# TinyHusk.net
KiCad netlist of a schematic drawn in EAGLE
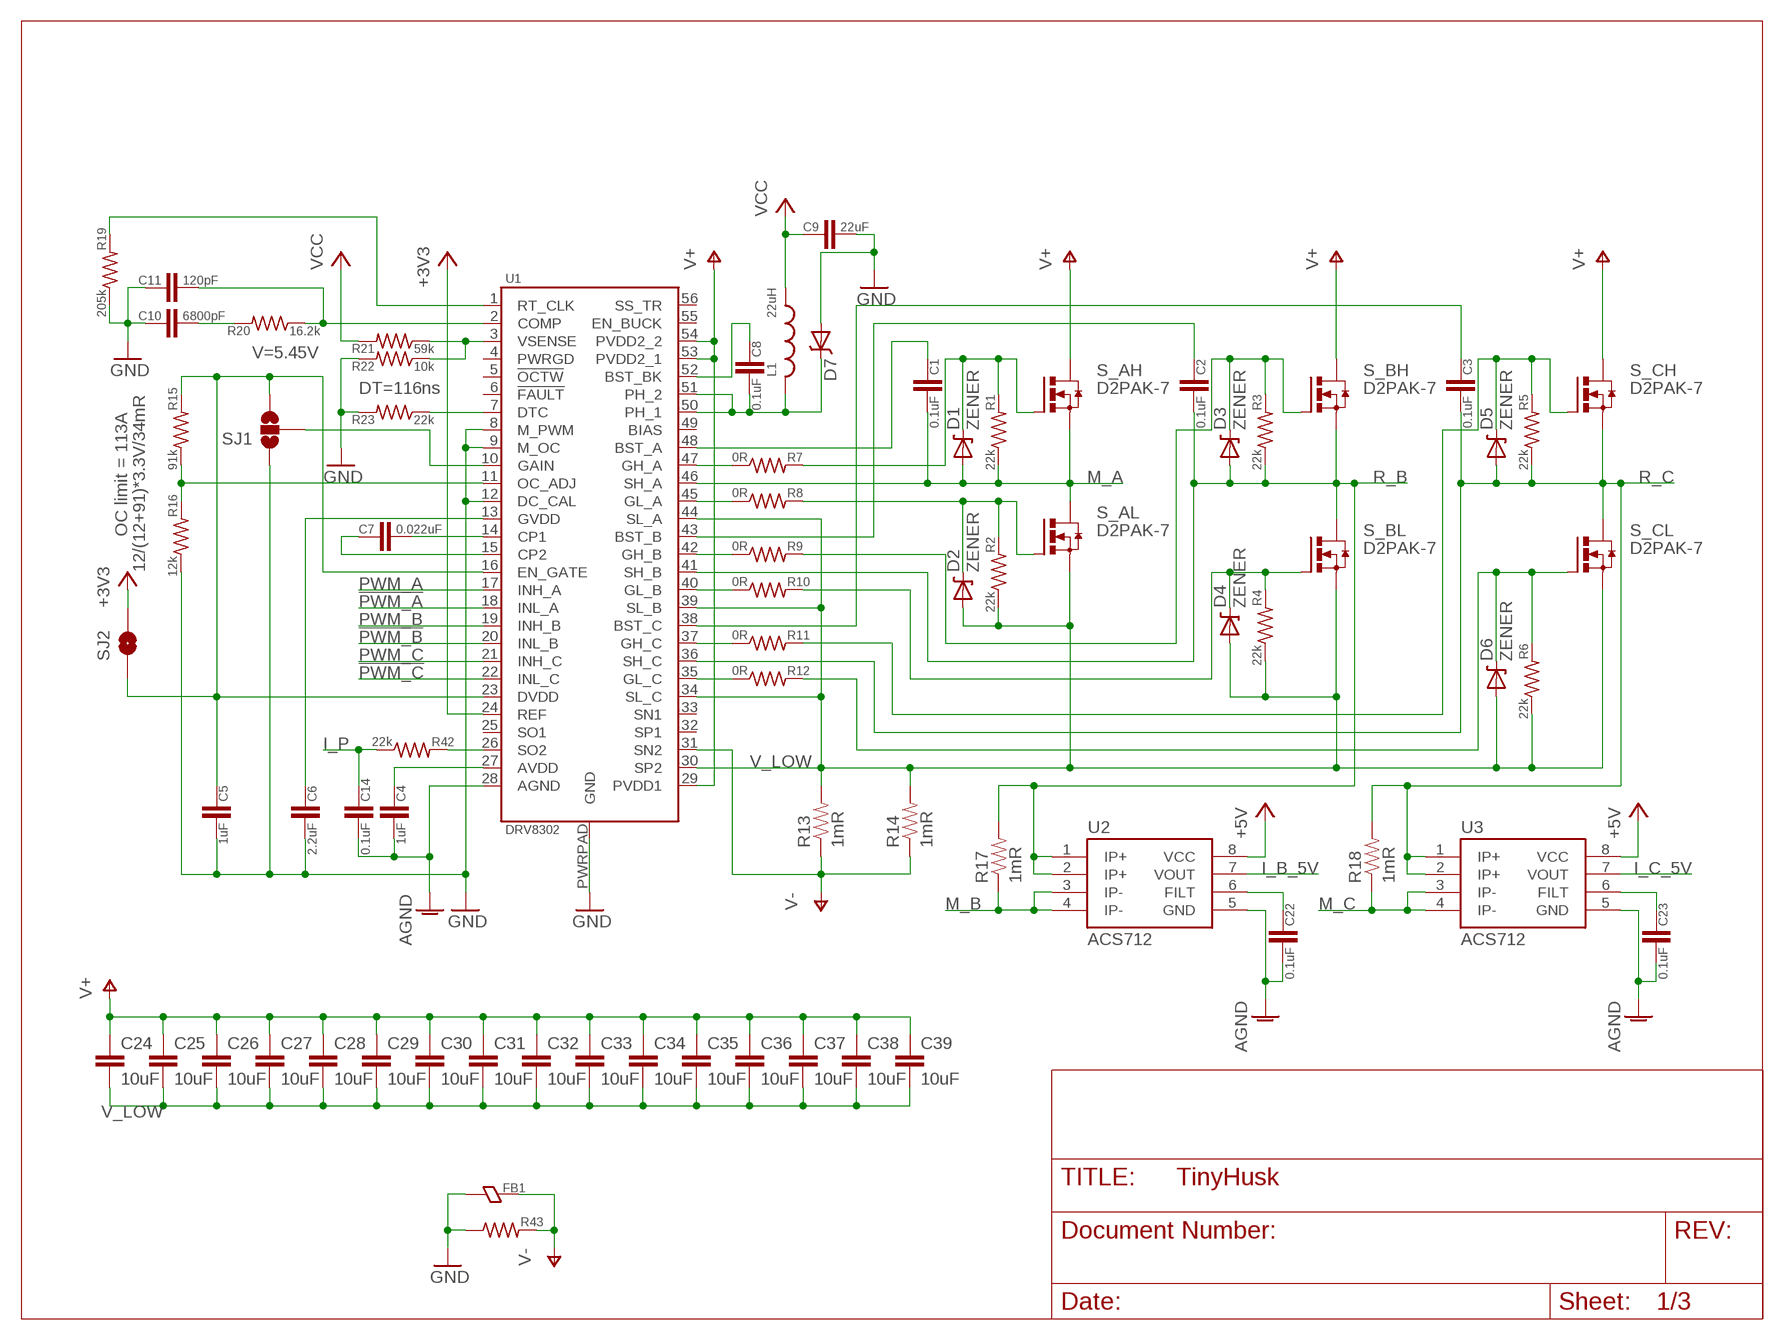
[diagram p0: schematic, sheet 1]
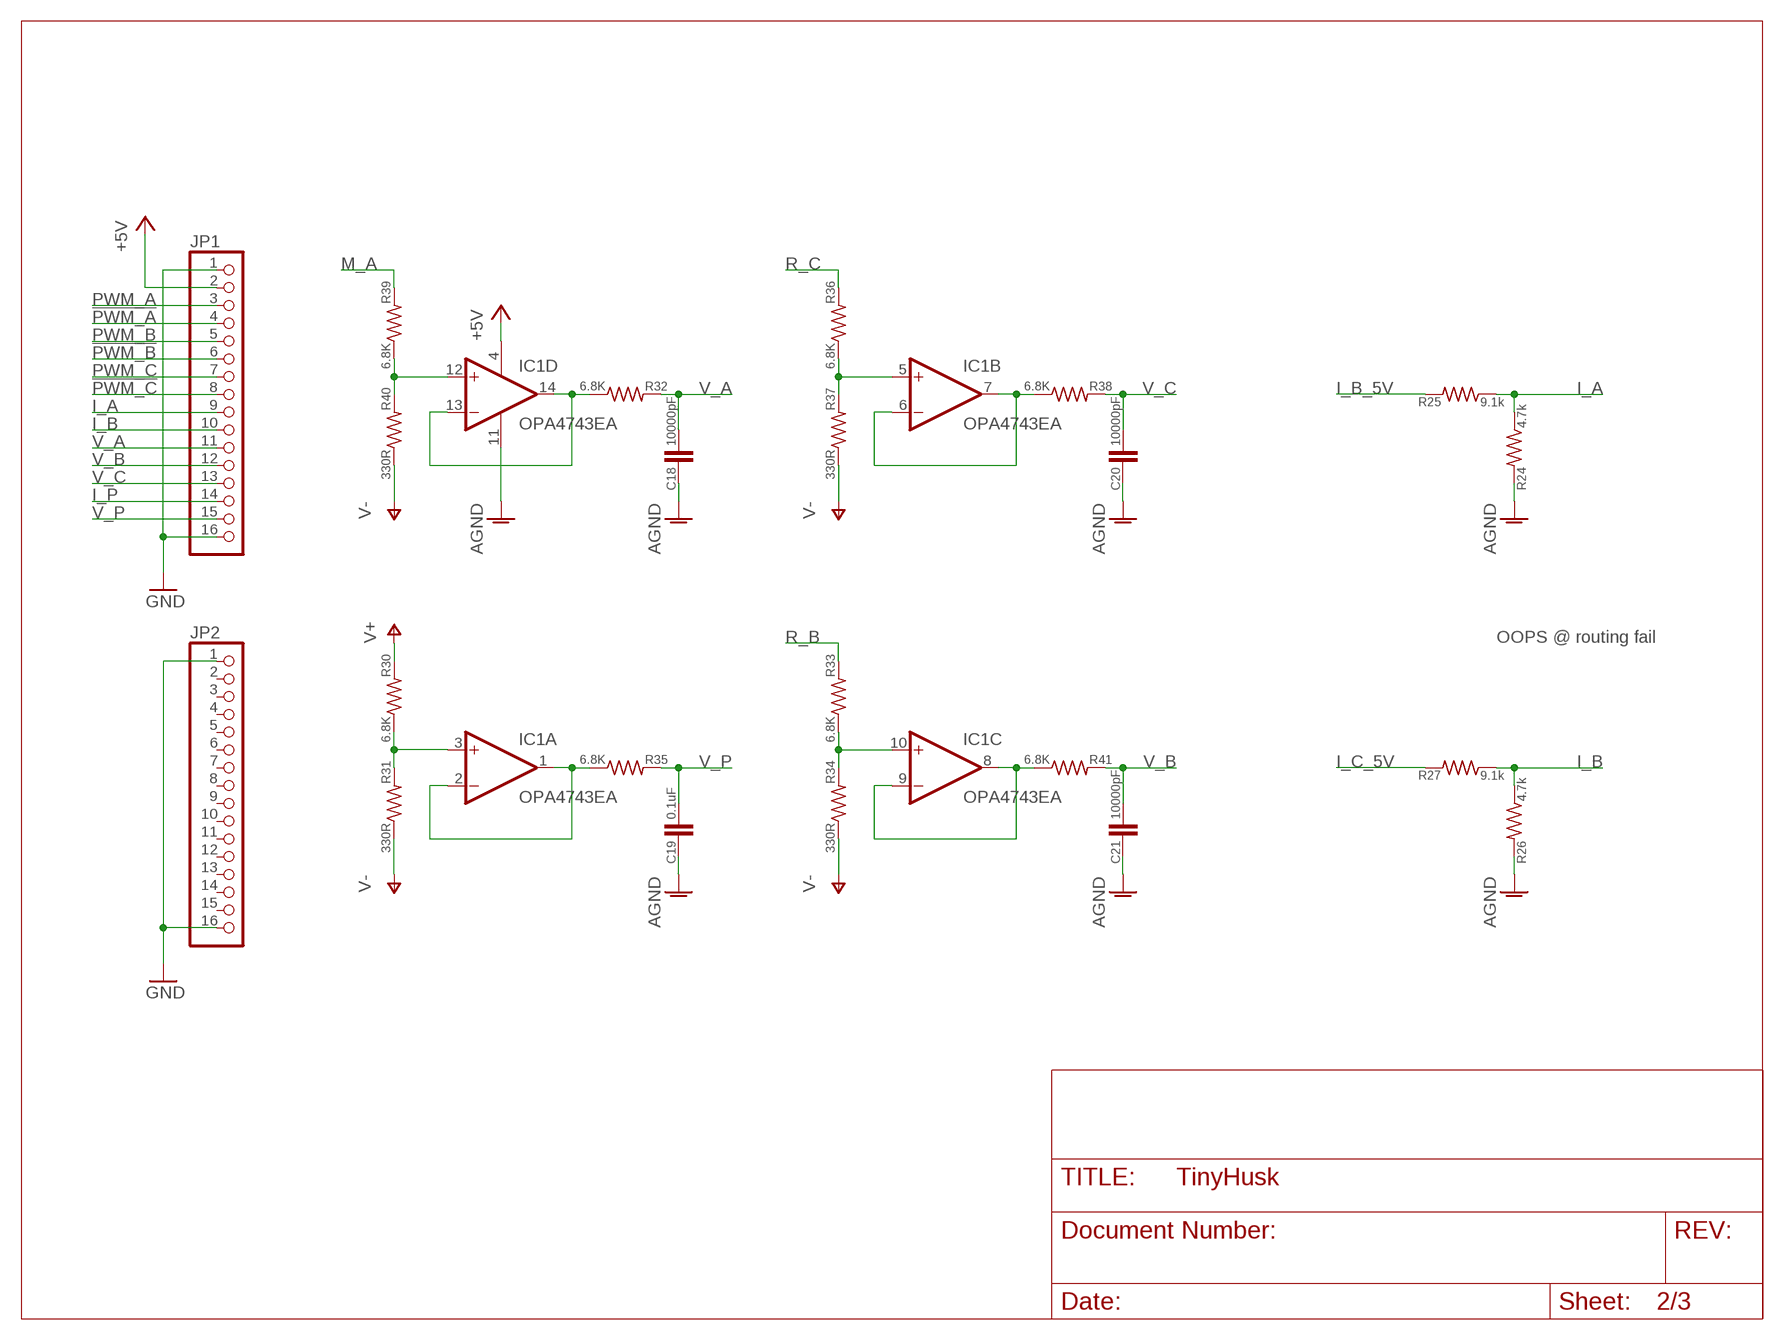
[diagram p1: schematic, sheet 2]
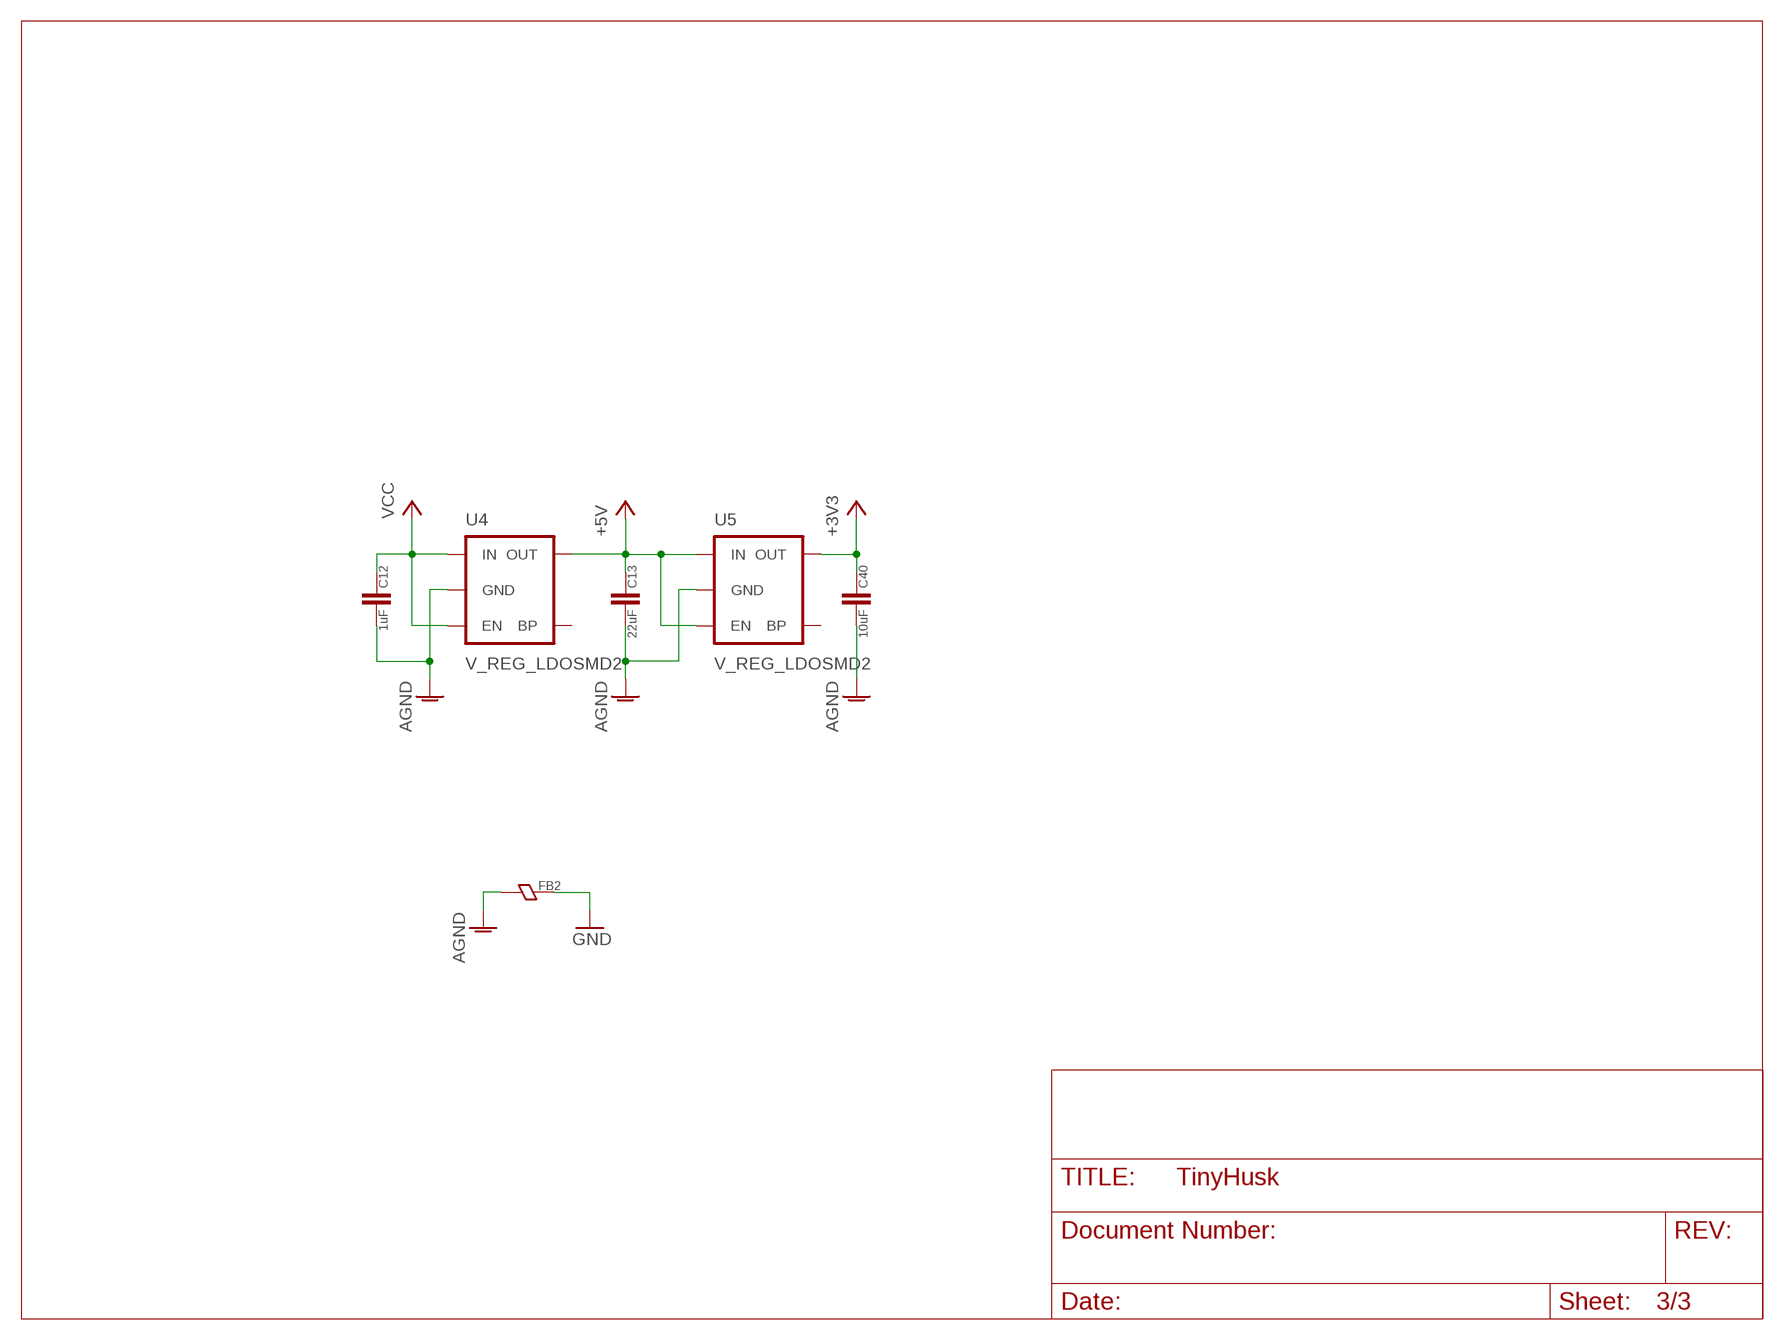
[diagram p2: schematic, sheet 3]

(export (version "E")
  (design (tool "Eeschema 10.0.6"))
  (components
    (comp (ref "C1")
      (value "0.1uF")
      (footprint "eagle-import:0603")
      (libsource (lib "eagle-import") (part "C0603"))
    )
    (comp (ref "C2")
      (value "0.1uF")
      (footprint "eagle-import:0603")
      (libsource (lib "eagle-import") (part "C0603"))
    )
    (comp (ref "C3")
      (value "0.1uF")
      (footprint "eagle-import:0603")
      (libsource (lib "eagle-import") (part "C0603"))
    )
    (comp (ref "C4")
      (value "1uF")
      (footprint "eagle-import:0603")
      (libsource (lib "eagle-import") (part "C0603"))
    )
    (comp (ref "C5")
      (value "1uF")
      (footprint "eagle-import:0603")
      (libsource (lib "eagle-import") (part "C0603"))
    )
    (comp (ref "C6")
      (value "2.2uF")
      (footprint "eagle-import:0603")
      (libsource (lib "eagle-import") (part "C0603"))
    )
    (comp (ref "C7")
      (value "0.022uF")
      (footprint "eagle-import:0603")
      (libsource (lib "eagle-import") (part "C0603"))
    )
    (comp (ref "C8")
      (value "0.1uF")
      (footprint "eagle-import:0603")
      (libsource (lib "eagle-import") (part "C0603"))
    )
    (comp (ref "C9")
      (value "22uF")
      (footprint "eagle-import:0805")
      (libsource (lib "eagle-import") (part "C0805"))
    )
    (comp (ref "C10")
      (value "6800pF")
      (footprint "eagle-import:0603")
      (libsource (lib "eagle-import") (part "C0603"))
    )
    (comp (ref "C11")
      (value "120pF")
      (footprint "eagle-import:0603")
      (libsource (lib "eagle-import") (part "C0603"))
    )
    (comp (ref "C14")
      (value "0.1uF")
      (footprint "eagle-import:0603")
      (libsource (lib "eagle-import") (part "C0603"))
    )
    (comp (ref "C22")
      (value "0.1uF")
      (footprint "eagle-import:0603")
      (libsource (lib "eagle-import") (part "C0603"))
    )
    (comp (ref "C23")
      (value "0.1uF")
      (footprint "eagle-import:0603")
      (libsource (lib "eagle-import") (part "C0603"))
    )
    (comp (ref "C24")
      (value "10uF")
      (footprint "eagle-import:1210")
      (libsource (lib "eagle-import") (part "CAP1210"))
    )
    (comp (ref "C25")
      (value "10uF")
      (footprint "eagle-import:1210")
      (libsource (lib "eagle-import") (part "CAP1210"))
    )
    (comp (ref "C26")
      (value "10uF")
      (footprint "eagle-import:1210")
      (libsource (lib "eagle-import") (part "CAP1210"))
    )
    (comp (ref "C27")
      (value "10uF")
      (footprint "eagle-import:1210")
      (libsource (lib "eagle-import") (part "CAP1210"))
    )
    (comp (ref "C28")
      (value "10uF")
      (footprint "eagle-import:1210")
      (libsource (lib "eagle-import") (part "CAP1210"))
    )
    (comp (ref "C29")
      (value "10uF")
      (footprint "eagle-import:1210")
      (libsource (lib "eagle-import") (part "CAP1210"))
    )
    (comp (ref "C30")
      (value "10uF")
      (footprint "eagle-import:1210")
      (libsource (lib "eagle-import") (part "CAP1210"))
    )
    (comp (ref "C31")
      (value "10uF")
      (footprint "eagle-import:1210")
      (libsource (lib "eagle-import") (part "CAP1210"))
    )
    (comp (ref "C32")
      (value "10uF")
      (footprint "eagle-import:1210")
      (libsource (lib "eagle-import") (part "CAP1210"))
    )
    (comp (ref "C33")
      (value "10uF")
      (footprint "eagle-import:1210")
      (libsource (lib "eagle-import") (part "CAP1210"))
    )
    (comp (ref "C34")
      (value "10uF")
      (footprint "eagle-import:1210")
      (libsource (lib "eagle-import") (part "CAP1210"))
    )
    (comp (ref "C35")
      (value "10uF")
      (footprint "eagle-import:1210")
      (libsource (lib "eagle-import") (part "CAP1210"))
    )
    (comp (ref "C36")
      (value "10uF")
      (footprint "eagle-import:1210")
      (libsource (lib "eagle-import") (part "CAP1210"))
    )
    (comp (ref "C37")
      (value "10uF")
      (footprint "eagle-import:1210")
      (libsource (lib "eagle-import") (part "CAP1210"))
    )
    (comp (ref "C38")
      (value "10uF")
      (footprint "eagle-import:1210")
      (libsource (lib "eagle-import") (part "CAP1210"))
    )
    (comp (ref "C39")
      (value "10uF")
      (footprint "eagle-import:1210")
      (libsource (lib "eagle-import") (part "CAP1210"))
    )
    (comp (ref "D1")
      (value "ZENER")
      (footprint "eagle-import:SOD-323")
      (libsource (lib "eagle-import") (part "DIODE-ZENER-BZT52"))
    )
    (comp (ref "D2")
      (value "ZENER")
      (footprint "eagle-import:SOD-323")
      (libsource (lib "eagle-import") (part "DIODE-ZENER-BZT52"))
    )
    (comp (ref "D3")
      (value "ZENER")
      (footprint "eagle-import:SOD-323")
      (libsource (lib "eagle-import") (part "DIODE-ZENER-BZT52"))
    )
    (comp (ref "D4")
      (value "ZENER")
      (footprint "eagle-import:SOD-323")
      (libsource (lib "eagle-import") (part "DIODE-ZENER-BZT52"))
    )
    (comp (ref "D5")
      (value "ZENER")
      (footprint "eagle-import:SOD-323")
      (libsource (lib "eagle-import") (part "DIODE-ZENER-BZT52"))
    )
    (comp (ref "D6")
      (value "ZENER")
      (footprint "eagle-import:SOD-323")
      (libsource (lib "eagle-import") (part "DIODE-ZENER-BZT52"))
    )
    (comp (ref "D7")
      (value "DIODE-SCHOTTKY_")
      (footprint "eagle-import:SMA-DIODE")
      (libsource (lib "eagle-import") (part "DIODE-SCHOTTKY_"))
    )
    (comp (ref "FB1")
      (value "FERRITE0603")
      (footprint "eagle-import:0603")
      (libsource (lib "eagle-import") (part "FERRITE0603"))
    )
    (comp (ref "L1")
      (value "22uH")
      (footprint "eagle-import:TAIYO-YUDEN_NR50")
      (libsource (lib "eagle-import") (part "L-US_TAIYO-YUDEN_NR50"))
    )
    (comp (ref "R1")
      (value "22k")
      (footprint "eagle-import:0603")
      (libsource (lib "eagle-import") (part "R0603"))
    )
    (comp (ref "R2")
      (value "22k")
      (footprint "eagle-import:0603")
      (libsource (lib "eagle-import") (part "R0603"))
    )
    (comp (ref "R3")
      (value "22k")
      (footprint "eagle-import:0603")
      (libsource (lib "eagle-import") (part "R0603"))
    )
    (comp (ref "R4")
      (value "22k")
      (footprint "eagle-import:0603")
      (libsource (lib "eagle-import") (part "R0603"))
    )
    (comp (ref "R5")
      (value "22k")
      (footprint "eagle-import:0603")
      (libsource (lib "eagle-import") (part "R0603"))
    )
    (comp (ref "R6")
      (value "22k")
      (footprint "eagle-import:0603")
      (libsource (lib "eagle-import") (part "R0603"))
    )
    (comp (ref "R7")
      (value "0R")
      (footprint "eagle-import:0603")
      (libsource (lib "eagle-import") (part "R0603"))
    )
    (comp (ref "R8")
      (value "0R")
      (footprint "eagle-import:0603")
      (libsource (lib "eagle-import") (part "R0603"))
    )
    (comp (ref "R9")
      (value "0R")
      (footprint "eagle-import:0603")
      (libsource (lib "eagle-import") (part "R0603"))
    )
    (comp (ref "R10")
      (value "0R")
      (footprint "eagle-import:0603")
      (libsource (lib "eagle-import") (part "R0603"))
    )
    (comp (ref "R11")
      (value "0R")
      (footprint "eagle-import:0603")
      (libsource (lib "eagle-import") (part "R0603"))
    )
    (comp (ref "R12")
      (value "0R")
      (footprint "eagle-import:0603")
      (libsource (lib "eagle-import") (part "R0603"))
    )
    (comp (ref "R13")
      (value "1mR")
      (footprint "eagle-import:R2512")
      (libsource (lib "eagle-import") (part "RESISTOR2512"))
    )
    (comp (ref "R14")
      (value "1mR")
      (footprint "eagle-import:R2512")
      (libsource (lib "eagle-import") (part "RESISTOR2512"))
    )
    (comp (ref "R15")
      (value "91k")
      (footprint "eagle-import:0603")
      (libsource (lib "eagle-import") (part "R0603"))
    )
    (comp (ref "R16")
      (value "12k")
      (footprint "eagle-import:0603")
      (libsource (lib "eagle-import") (part "R0603"))
    )
    (comp (ref "R17")
      (value "1mR")
      (footprint "eagle-import:R2512")
      (libsource (lib "eagle-import") (part "RESISTOR2512"))
    )
    (comp (ref "R18")
      (value "1mR")
      (footprint "eagle-import:R2512")
      (libsource (lib "eagle-import") (part "RESISTOR2512"))
    )
    (comp (ref "R19")
      (value "205k")
      (footprint "eagle-import:0603")
      (libsource (lib "eagle-import") (part "R0603"))
    )
    (comp (ref "R20")
      (value "16.2k")
      (footprint "eagle-import:0603")
      (libsource (lib "eagle-import") (part "R0603"))
    )
    (comp (ref "R21")
      (value "59k")
      (footprint "eagle-import:0603")
      (libsource (lib "eagle-import") (part "R0603"))
    )
    (comp (ref "R22")
      (value "10k")
      (footprint "eagle-import:0603")
      (libsource (lib "eagle-import") (part "R0603"))
    )
    (comp (ref "R23")
      (value "22k")
      (footprint "eagle-import:0603")
      (libsource (lib "eagle-import") (part "R0603"))
    )
    (comp (ref "R42")
      (value "22k")
      (footprint "eagle-import:0603")
      (libsource (lib "eagle-import") (part "R0603"))
    )
    (comp (ref "R43")
      (value "R0603")
      (footprint "eagle-import:0603")
      (libsource (lib "eagle-import") (part "R0603"))
    )
    (comp (ref "SJ1")
      (value "SOLDERJUMPER_2WAYS")
      (footprint "eagle-import:SJ_X")
      (libsource (lib "eagle-import") (part "SOLDERJUMPER_2WAYS"))
    )
    (comp (ref "SJ2")
      (value "SOLDERJUMPERTRACE")
      (footprint "eagle-import:SJ_2S-TRACE")
      (libsource (lib "eagle-import") (part "SOLDERJUMPERTRACE"))
    )
    (comp (ref "S_AH")
      (value "D2PAK-7")
      (footprint "eagle-import:D2PAK-7")
      (libsource (lib "eagle-import") (part "MOSFET-ND2PAK7"))
    )
    (comp (ref "S_AL")
      (value "D2PAK-7")
      (footprint "eagle-import:D2PAK-7")
      (libsource (lib "eagle-import") (part "MOSFET-ND2PAK7"))
    )
    (comp (ref "S_BH")
      (value "D2PAK-7")
      (footprint "eagle-import:D2PAK-7")
      (libsource (lib "eagle-import") (part "MOSFET-ND2PAK7"))
    )
    (comp (ref "S_BL")
      (value "D2PAK-7")
      (footprint "eagle-import:D2PAK-7")
      (libsource (lib "eagle-import") (part "MOSFET-ND2PAK7"))
    )
    (comp (ref "S_CH")
      (value "D2PAK-7")
      (footprint "eagle-import:D2PAK-7")
      (libsource (lib "eagle-import") (part "MOSFET-ND2PAK7"))
    )
    (comp (ref "S_CL")
      (value "D2PAK-7")
      (footprint "eagle-import:D2PAK-7")
      (libsource (lib "eagle-import") (part "MOSFET-ND2PAK7"))
    )
    (comp (ref "U1")
      (value "DRV8302")
      (footprint "eagle-import:HTSSOP-56")
      (libsource (lib "eagle-import") (part "DRV8302"))
    )
    (comp (ref "U2")
      (value "ACS712")
      (footprint "eagle-import:SO08")
      (libsource (lib "eagle-import") (part "ACS712"))
    )
    (comp (ref "U3")
      (value "ACS712")
      (footprint "eagle-import:SO08")
      (libsource (lib "eagle-import") (part "ACS712"))
    )
    (comp (ref "C12")
      (value "1uF")
      (footprint "eagle-import:0603")
      (libsource (lib "eagle-import") (part "C0603"))
    )
    (comp (ref "C13")
      (value "22uF")
      (footprint "eagle-import:0805")
      (libsource (lib "eagle-import") (part "C0805"))
    )
    (comp (ref "C40")
      (value "10uF")
      (footprint "eagle-import:0603")
      (libsource (lib "eagle-import") (part "C0603"))
    )
    (comp (ref "FB2")
      (value "FERRITE0603")
      (footprint "eagle-import:0603")
      (libsource (lib "eagle-import") (part "FERRITE0603"))
    )
    (comp (ref "U4")
      (value "V_REG_LDOSMD2")
      (footprint "eagle-import:SC70")
      (libsource (lib "eagle-import") (part "V_REG_LDOSMD2"))
    )
    (comp (ref "U5")
      (value "V_REG_LDOSMD2")
      (footprint "eagle-import:SC70")
      (libsource (lib "eagle-import") (part "V_REG_LDOSMD2"))
    )
    (comp (ref "C18")
      (value "10000pF")
      (footprint "eagle-import:0603")
      (libsource (lib "eagle-import") (part "C0603"))
    )
    (comp (ref "C19")
      (value "0.1uF")
      (footprint "eagle-import:0603")
      (libsource (lib "eagle-import") (part "C0603"))
    )
    (comp (ref "C20")
      (value "10000pF")
      (footprint "eagle-import:0603")
      (libsource (lib "eagle-import") (part "C0603"))
    )
    (comp (ref "C21")
      (value "10000pF")
      (footprint "eagle-import:0603")
      (libsource (lib "eagle-import") (part "C0603"))
    )
    (comp (ref "IC1")
      (value "OPA4743EA")
      (footprint "eagle-import:TSSOP14")
      (libsource (lib "eagle-import") (part "OPA4743EA"))
    )
    (comp (ref "JP1")
      (value "PINHD-1X16_2.54-S")
      (footprint "eagle-import:1X16-S")
      (libsource (lib "eagle-import") (part "PINHD-1X16_2.54-S"))
    )
    (comp (ref "JP2")
      (value "PINHD-1X16_2.54-S")
      (footprint "eagle-import:1X16-S")
      (libsource (lib "eagle-import") (part "PINHD-1X16_2.54-S"))
    )
    (comp (ref "R24")
      (value "4.7k")
      (footprint "eagle-import:0603")
      (libsource (lib "eagle-import") (part "R0603"))
    )
    (comp (ref "R25")
      (value "9.1k")
      (footprint "eagle-import:0603")
      (libsource (lib "eagle-import") (part "R0603"))
    )
    (comp (ref "R26")
      (value "4.7k")
      (footprint "eagle-import:0603")
      (libsource (lib "eagle-import") (part "R0603"))
    )
    (comp (ref "R27")
      (value "9.1k")
      (footprint "eagle-import:0603")
      (libsource (lib "eagle-import") (part "R0603"))
    )
    (comp (ref "R30")
      (value "6.8K")
      (footprint "eagle-import:0603")
      (libsource (lib "eagle-import") (part "R0603"))
    )
    (comp (ref "R31")
      (value "330R")
      (footprint "eagle-import:0603")
      (libsource (lib "eagle-import") (part "R0603"))
    )
    (comp (ref "R32")
      (value "6.8K")
      (footprint "eagle-import:0603")
      (libsource (lib "eagle-import") (part "R0603"))
    )
    (comp (ref "R33")
      (value "6.8K")
      (footprint "eagle-import:0603")
      (libsource (lib "eagle-import") (part "R0603"))
    )
    (comp (ref "R34")
      (value "330R")
      (footprint "eagle-import:0603")
      (libsource (lib "eagle-import") (part "R0603"))
    )
    (comp (ref "R35")
      (value "6.8K")
      (footprint "eagle-import:0603")
      (libsource (lib "eagle-import") (part "R0603"))
    )
    (comp (ref "R36")
      (value "6.8K")
      (footprint "eagle-import:0603")
      (libsource (lib "eagle-import") (part "R0603"))
    )
    (comp (ref "R37")
      (value "330R")
      (footprint "eagle-import:0603")
      (libsource (lib "eagle-import") (part "R0603"))
    )
    (comp (ref "R38")
      (value "6.8K")
      (footprint "eagle-import:0603")
      (libsource (lib "eagle-import") (part "R0603"))
    )
    (comp (ref "R39")
      (value "6.8K")
      (footprint "eagle-import:0603")
      (libsource (lib "eagle-import") (part "R0603"))
    )
    (comp (ref "R40")
      (value "330R")
      (footprint "eagle-import:0603")
      (libsource (lib "eagle-import") (part "R0603"))
    )
    (comp (ref "R41")
      (value "6.8K")
      (footprint "eagle-import:0603")
      (libsource (lib "eagle-import") (part "R0603"))
    )
  )
  (nets
    (net (code "1") (name "+3V3") (class "Default")
      (node (ref "C40") (pin "1") (pinfunction "1_1") (pintype "passive"))
      (node (ref "SJ2") (pin "2") (pinfunction "2_2") (pintype "passive"))
      (node (ref "U1") (pin "24") (pinfunction "REF_24") (pintype "input"))
      (node (ref "U5") (pin "5") (pinfunction "OUT_5") (pintype "passive"))
    )
    (net (code "2") (name "+5V") (class "Default")
      (node (ref "C13") (pin "1") (pinfunction "1_1") (pintype "passive"))
      (node (ref "IC1") (pin "4") (pinfunction "V+_4") (pintype "power_in"))
      (node (ref "JP1") (pin "2") (pinfunction "2_2") (pintype "passive"))
      (node (ref "U2") (pin "8") (pinfunction "VCC_8") (pintype "bidirectional"))
      (node (ref "U3") (pin "8") (pinfunction "VCC_8") (pintype "bidirectional"))
      (node (ref "U4") (pin "5") (pinfunction "OUT_5") (pintype "passive"))
      (node (ref "U5") (pin "1") (pinfunction "IN_1") (pintype "input"))
      (node (ref "U5") (pin "3") (pinfunction "EN_3") (pintype "input"))
    )
    (net (code "3") (name "AGND") (class "Default")
      (node (ref "C12") (pin "2") (pinfunction "2_2") (pintype "passive"))
      (node (ref "C13") (pin "2") (pinfunction "2_2") (pintype "passive"))
      (node (ref "C14") (pin "2") (pinfunction "2_2") (pintype "passive"))
      (node (ref "C18") (pin "1") (pinfunction "1_1") (pintype "passive"))
      (node (ref "C19") (pin "1") (pinfunction "1_1") (pintype "passive"))
      (node (ref "C20") (pin "1") (pinfunction "1_1") (pintype "passive"))
      (node (ref "C21") (pin "1") (pinfunction "1_1") (pintype "passive"))
      (node (ref "C22") (pin "2") (pinfunction "2_2") (pintype "passive"))
      (node (ref "C23") (pin "2") (pinfunction "2_2") (pintype "passive"))
      (node (ref "C4") (pin "2") (pinfunction "2_2") (pintype "passive"))
      (node (ref "C40") (pin "2") (pinfunction "2_2") (pintype "passive"))
      (node (ref "FB2") (pin "1") (pinfunction "1_1") (pintype "passive"))
      (node (ref "IC1") (pin "11") (pinfunction "V-_11") (pintype "power_in"))
      (node (ref "R24") (pin "2") (pinfunction "2_2") (pintype "passive"))
      (node (ref "R26") (pin "2") (pinfunction "2_2") (pintype "passive"))
      (node (ref "U1") (pin "28") (pinfunction "AGND_28") (pintype "power_in"))
      (node (ref "U2") (pin "5") (pinfunction "GND_5") (pintype "bidirectional"))
      (node (ref "U3") (pin "5") (pinfunction "GND_5") (pintype "bidirectional"))
      (node (ref "U4") (pin "2") (pinfunction "GND_2") (pintype "input"))
      (node (ref "U5") (pin "2") (pinfunction "GND_2") (pintype "input"))
    )
    (net (code "4") (name "GND") (class "Default")
      (node (ref "C10") (pin "1") (pinfunction "1_1") (pintype "passive"))
      (node (ref "C11") (pin "1") (pinfunction "1_1") (pintype "passive"))
      (node (ref "C5") (pin "2") (pinfunction "2_2") (pintype "passive"))
      (node (ref "C6") (pin "2") (pinfunction "2_2") (pintype "passive"))
      (node (ref "C9") (pin "2") (pinfunction "2_2") (pintype "passive"))
      (node (ref "D7") (pin "A") (pinfunction "A_A") (pintype "passive"))
      (node (ref "FB1") (pin "1") (pinfunction "1_1") (pintype "passive"))
      (node (ref "FB2") (pin "2") (pinfunction "2_2") (pintype "passive"))
      (node (ref "JP1") (pin "1") (pinfunction "1_1") (pintype "passive"))
      (node (ref "JP1") (pin "16") (pinfunction "16_16") (pintype "passive"))
      (node (ref "JP2") (pin "1") (pinfunction "1_1") (pintype "passive"))
      (node (ref "JP2") (pin "16") (pinfunction "16_16") (pintype "passive"))
      (node (ref "R16") (pin "1") (pinfunction "1_1") (pintype "passive"))
      (node (ref "R19") (pin "1") (pinfunction "1_1") (pintype "passive"))
      (node (ref "R22") (pin "2") (pinfunction "2_2") (pintype "passive"))
      (node (ref "R23") (pin "2") (pinfunction "2_2") (pintype "passive"))
      (node (ref "R43") (pin "1") (pinfunction "1_1") (pintype "passive"))
      (node (ref "SJ1") (pin "1") (pinfunction "1_1") (pintype "passive"))
      (node (ref "U1") (pin "12") (pinfunction "DC_CAL_12") (pintype "input"))
      (node (ref "U1") (pin "8") (pinfunction "M_PWM_8") (pintype "input"))
      (node (ref "U1") (pin "9") (pinfunction "M_OC_9") (pintype "input"))
      (node (ref "U1") (pin "PWRPAD") (pinfunction "GND_PWRPAD") (pintype "power_in"))
    )
    (net (code "5") (name "I_A") (class "Default")
      (node (ref "JP1") (pin "9") (pinfunction "9_9") (pintype "passive"))
      (node (ref "R24") (pin "1") (pinfunction "1_1") (pintype "passive"))
      (node (ref "R25") (pin "1") (pinfunction "1_1") (pintype "passive"))
    )
    (net (code "6") (name "I_B") (class "Default")
      (node (ref "JP1") (pin "10") (pinfunction "10_10") (pintype "passive"))
      (node (ref "R26") (pin "1") (pinfunction "1_1") (pintype "passive"))
      (node (ref "R27") (pin "1") (pinfunction "1_1") (pintype "passive"))
    )
    (net (code "7") (name "I_B_5V") (class "Default")
      (node (ref "R25") (pin "2") (pinfunction "2_2") (pintype "passive"))
      (node (ref "U2") (pin "7") (pinfunction "VOUT_7") (pintype "bidirectional"))
    )
    (net (code "8") (name "I_C_5V") (class "Default")
      (node (ref "R27") (pin "2") (pinfunction "2_2") (pintype "passive"))
      (node (ref "U3") (pin "7") (pinfunction "VOUT_7") (pintype "bidirectional"))
    )
    (net (code "9") (name "I_P") (class "Default")
      (node (ref "C14") (pin "1") (pinfunction "1_1") (pintype "passive"))
      (node (ref "JP1") (pin "14") (pinfunction "14_14") (pintype "passive"))
      (node (ref "R42") (pin "1") (pinfunction "1_1") (pintype "passive"))
    )
    (net (code "10") (name "M_A") (class "Default")
      (node (ref "C1") (pin "2") (pinfunction "2_2") (pintype "passive"))
      (node (ref "D1") (pin "2") (pinfunction "A_2") (pintype "passive"))
      (node (ref "R1") (pin "1") (pinfunction "1_1") (pintype "passive"))
      (node (ref "R39") (pin "2") (pinfunction "2_2") (pintype "passive"))
      (node (ref "S_AH") (pin "2") (pinfunction "S_2") (pintype "passive"))
      (node (ref "S_AH") (pin "3") (pinfunction "S_3") (pintype "passive"))
      (node (ref "S_AH") (pin "5") (pinfunction "S_5") (pintype "passive"))
      (node (ref "S_AH") (pin "6") (pinfunction "S_6") (pintype "passive"))
      (node (ref "S_AH") (pin "7") (pinfunction "S_7") (pintype "passive"))
      (node (ref "S_AL") (pin "4") (pinfunction "D_4") (pintype "passive"))
      (node (ref "U1") (pin "46") (pinfunction "SH_A_46") (pintype "input"))
    )
    (net (code "11") (name "M_B") (class "Default")
      (node (ref "R17") (pin "1") (pinfunction "1_1") (pintype "passive"))
      (node (ref "U2") (pin "3") (pinfunction "IP-_3") (pintype "bidirectional"))
      (node (ref "U2") (pin "4") (pinfunction "IP-_4") (pintype "bidirectional"))
    )
    (net (code "12") (name "M_C") (class "Default")
      (node (ref "R18") (pin "1") (pinfunction "1_1") (pintype "passive"))
      (node (ref "U3") (pin "3") (pinfunction "IP-_3") (pintype "bidirectional"))
      (node (ref "U3") (pin "4") (pinfunction "IP-_4") (pintype "bidirectional"))
    )
    (net (code "13") (name "Net-(C10-Pad2)") (class "Default")
      (node (ref "C10") (pin "2") (pinfunction "2_2") (pintype "passive"))
      (node (ref "R20") (pin "2") (pinfunction "2_2") (pintype "passive"))
    )
    (net (code "14") (name "Net-(D1-C)") (class "Default")
      (node (ref "D1") (pin "1") (pinfunction "C_1") (pintype "passive"))
      (node (ref "R1") (pin "2") (pinfunction "2_2") (pintype "passive"))
      (node (ref "R7") (pin "2") (pinfunction "2_2") (pintype "passive"))
      (node (ref "S_AH") (pin "1") (pinfunction "G_1") (pintype "passive"))
    )
    (net (code "15") (name "Net-(D2-C)") (class "Default")
      (node (ref "D2") (pin "1") (pinfunction "C_1") (pintype "passive"))
      (node (ref "R2") (pin "2") (pinfunction "2_2") (pintype "passive"))
      (node (ref "R8") (pin "2") (pinfunction "2_2") (pintype "passive"))
      (node (ref "S_AL") (pin "1") (pinfunction "G_1") (pintype "passive"))
    )
    (net (code "16") (name "Net-(D3-C)") (class "Default")
      (node (ref "D3") (pin "1") (pinfunction "C_1") (pintype "passive"))
      (node (ref "R3") (pin "2") (pinfunction "2_2") (pintype "passive"))
      (node (ref "R9") (pin "2") (pinfunction "2_2") (pintype "passive"))
      (node (ref "S_BH") (pin "1") (pinfunction "G_1") (pintype "passive"))
    )
    (net (code "17") (name "Net-(D4-C)") (class "Default")
      (node (ref "D4") (pin "1") (pinfunction "C_1") (pintype "passive"))
      (node (ref "R10") (pin "2") (pinfunction "2_2") (pintype "passive"))
      (node (ref "R4") (pin "2") (pinfunction "2_2") (pintype "passive"))
      (node (ref "S_BL") (pin "1") (pinfunction "G_1") (pintype "passive"))
    )
    (net (code "18") (name "Net-(D5-C)") (class "Default")
      (node (ref "D5") (pin "1") (pinfunction "C_1") (pintype "passive"))
      (node (ref "R11") (pin "2") (pinfunction "2_2") (pintype "passive"))
      (node (ref "R5") (pin "2") (pinfunction "2_2") (pintype "passive"))
      (node (ref "S_CH") (pin "1") (pinfunction "G_1") (pintype "passive"))
    )
    (net (code "19") (name "Net-(D6-C)") (class "Default")
      (node (ref "D6") (pin "1") (pinfunction "C_1") (pintype "passive"))
      (node (ref "R12") (pin "2") (pinfunction "2_2") (pintype "passive"))
      (node (ref "R6") (pin "2") (pinfunction "2_2") (pintype "passive"))
      (node (ref "S_CL") (pin "1") (pinfunction "G_1") (pintype "passive"))
    )
    (net (code "20") (name "Net-(IC1A-+IN)") (class "Default")
      (node (ref "IC1") (pin "3") (pinfunction "+IN_3") (pintype "input"))
      (node (ref "R30") (pin "1") (pinfunction "1_1") (pintype "passive"))
      (node (ref "R31") (pin "2") (pinfunction "2_2") (pintype "passive"))
    )
    (net (code "21") (name "Net-(IC1A--IN)") (class "Default")
      (node (ref "IC1") (pin "1") (pinfunction "OUT_1") (pintype "output"))
      (node (ref "IC1") (pin "2") (pinfunction "-IN_2") (pintype "input"))
      (node (ref "R35") (pin "1") (pinfunction "1_1") (pintype "passive"))
    )
    (net (code "22") (name "Net-(IC1B-+IN)") (class "Default")
      (node (ref "IC1") (pin "5") (pinfunction "+IN_5") (pintype "input"))
      (node (ref "R36") (pin "1") (pinfunction "1_1") (pintype "passive"))
      (node (ref "R37") (pin "2") (pinfunction "2_2") (pintype "passive"))
    )
    (net (code "23") (name "Net-(IC1B--IN)") (class "Default")
      (node (ref "IC1") (pin "6") (pinfunction "-IN_6") (pintype "input"))
      (node (ref "IC1") (pin "7") (pinfunction "OUT_7") (pintype "output"))
      (node (ref "R38") (pin "1") (pinfunction "1_1") (pintype "passive"))
    )
    (net (code "24") (name "Net-(IC1C-+IN)") (class "Default")
      (node (ref "IC1") (pin "10") (pinfunction "+IN_10") (pintype "input"))
      (node (ref "R33") (pin "1") (pinfunction "1_1") (pintype "passive"))
      (node (ref "R34") (pin "2") (pinfunction "2_2") (pintype "passive"))
    )
    (net (code "25") (name "Net-(IC1C--IN)") (class "Default")
      (node (ref "IC1") (pin "8") (pinfunction "OUT_8") (pintype "output"))
      (node (ref "IC1") (pin "9") (pinfunction "-IN_9") (pintype "input"))
      (node (ref "R41") (pin "1") (pinfunction "1_1") (pintype "passive"))
    )
    (net (code "26") (name "Net-(IC1D-+IN)") (class "Default")
      (node (ref "IC1") (pin "12") (pinfunction "+IN_12") (pintype "input"))
      (node (ref "R39") (pin "1") (pinfunction "1_1") (pintype "passive"))
      (node (ref "R40") (pin "2") (pinfunction "2_2") (pintype "passive"))
    )
    (net (code "27") (name "Net-(IC1D--IN)") (class "Default")
      (node (ref "IC1") (pin "13") (pinfunction "-IN_13") (pintype "input"))
      (node (ref "IC1") (pin "14") (pinfunction "OUT_14") (pintype "output"))
      (node (ref "R32") (pin "1") (pinfunction "1_1") (pintype "passive"))
    )
    (net (code "28") (name "Net-(L1-2)") (class "Default")
      (node (ref "C8") (pin "2") (pinfunction "2_2") (pintype "passive"))
      (node (ref "D7") (pin "C") (pinfunction "C_C") (pintype "passive"))
      (node (ref "L1") (pin "P$2") (pinfunction "2_P$2") (pintype "passive"))
      (node (ref "U1") (pin "50") (pinfunction "PH_1_50") (pintype "output"))
      (node (ref "U1") (pin "51") (pinfunction "PH_2_51") (pintype "output"))
    )
    (net (code "29") (name "Net-(U1-AVDD)") (class "Default")
      (node (ref "C4") (pin "1") (pinfunction "1_1") (pintype "passive"))
      (node (ref "U1") (pin "27") (pinfunction "AVDD_27") (pintype "power_in"))
    )
    (net (code "30") (name "Net-(U1-BST_A)") (class "Default")
      (node (ref "C1") (pin "1") (pinfunction "1_1") (pintype "passive"))
      (node (ref "U1") (pin "48") (pinfunction "BST_A_48") (pintype "power_in"))
    )
    (net (code "31") (name "Net-(U1-BST_B)") (class "Default")
      (node (ref "C2") (pin "1") (pinfunction "1_1") (pintype "passive"))
      (node (ref "U1") (pin "43") (pinfunction "BST_B_43") (pintype "power_in"))
    )
    (net (code "32") (name "Net-(U1-BST_BK)") (class "Default")
      (node (ref "C8") (pin "1") (pinfunction "1_1") (pintype "passive"))
      (node (ref "U1") (pin "52") (pinfunction "BST_BK_52") (pintype "power_in"))
    )
    (net (code "33") (name "Net-(U1-BST_C)") (class "Default")
      (node (ref "C3") (pin "1") (pinfunction "1_1") (pintype "passive"))
      (node (ref "U1") (pin "38") (pinfunction "BST_C_38") (pintype "power_in"))
    )
    (net (code "34") (name "Net-(U1-COMP)") (class "Default")
      (node (ref "C11") (pin "2") (pinfunction "2_2") (pintype "passive"))
      (node (ref "R20") (pin "1") (pinfunction "1_1") (pintype "passive"))
      (node (ref "U1") (pin "2") (pinfunction "COMP_2") (pintype "output"))
    )
    (net (code "35") (name "Net-(U1-CP1)") (class "Default")
      (node (ref "C7") (pin "2") (pinfunction "2_2") (pintype "passive"))
      (node (ref "U1") (pin "14") (pinfunction "CP1_14") (pintype "power_in"))
    )
    (net (code "36") (name "Net-(U1-CP2)") (class "Default")
      (node (ref "C7") (pin "1") (pinfunction "1_1") (pintype "passive"))
      (node (ref "U1") (pin "15") (pinfunction "CP2_15") (pintype "power_in"))
    )
    (net (code "37") (name "Net-(U1-DTC)") (class "Default")
      (node (ref "R23") (pin "1") (pinfunction "1_1") (pintype "passive"))
      (node (ref "U1") (pin "7") (pinfunction "DTC_7") (pintype "input"))
    )
    (net (code "38") (name "Net-(U1-DVDD)") (class "Default")
      (node (ref "C5") (pin "1") (pinfunction "1_1") (pintype "passive"))
      (node (ref "R15") (pin "2") (pinfunction "2_2") (pintype "passive"))
      (node (ref "SJ1") (pin "3") (pinfunction "3_3") (pintype "passive"))
      (node (ref "SJ2") (pin "1") (pinfunction "1_1") (pintype "passive"))
      (node (ref "U1") (pin "16") (pinfunction "EN_GATE_16") (pintype "input"))
      (node (ref "U1") (pin "23") (pinfunction "DVDD_23") (pintype "power_in"))
    )
    (net (code "39") (name "Net-(U1-GAIN)") (class "Default")
      (node (ref "SJ1") (pin "2") (pinfunction "2_2") (pintype "passive"))
      (node (ref "U1") (pin "10") (pinfunction "GAIN_10") (pintype "input"))
    )
    (net (code "40") (name "Net-(U1-GH_A)") (class "Default")
      (node (ref "R7") (pin "1") (pinfunction "1_1") (pintype "passive"))
      (node (ref "U1") (pin "47") (pinfunction "GH_A_47") (pintype "output"))
    )
    (net (code "41") (name "Net-(U1-GH_B)") (class "Default")
      (node (ref "R9") (pin "1") (pinfunction "1_1") (pintype "passive"))
      (node (ref "U1") (pin "42") (pinfunction "GH_B_42") (pintype "output"))
    )
    (net (code "42") (name "Net-(U1-GH_C)") (class "Default")
      (node (ref "R11") (pin "1") (pinfunction "1_1") (pintype "passive"))
      (node (ref "U1") (pin "37") (pinfunction "GH_C_37") (pintype "output"))
    )
    (net (code "43") (name "Net-(U1-GL_A)") (class "Default")
      (node (ref "R8") (pin "1") (pinfunction "1_1") (pintype "passive"))
      (node (ref "U1") (pin "45") (pinfunction "GL_A_45") (pintype "output"))
    )
    (net (code "44") (name "Net-(U1-GL_B)") (class "Default")
      (node (ref "R10") (pin "1") (pinfunction "1_1") (pintype "passive"))
      (node (ref "U1") (pin "40") (pinfunction "GL_B_40") (pintype "output"))
    )
    (net (code "45") (name "Net-(U1-GL_C)") (class "Default")
      (node (ref "R12") (pin "1") (pinfunction "1_1") (pintype "passive"))
      (node (ref "U1") (pin "35") (pinfunction "GL_C_35") (pintype "output"))
    )
    (net (code "46") (name "Net-(U1-GVDD)") (class "Default")
      (node (ref "C6") (pin "1") (pinfunction "1_1") (pintype "passive"))
      (node (ref "U1") (pin "13") (pinfunction "GVDD_13") (pintype "power_in"))
    )
    (net (code "47") (name "Net-(U1-OC_ADJ)") (class "Default")
      (node (ref "R15") (pin "1") (pinfunction "1_1") (pintype "passive"))
      (node (ref "R16") (pin "2") (pinfunction "2_2") (pintype "passive"))
      (node (ref "U1") (pin "11") (pinfunction "OC_ADJ_11") (pintype "input"))
    )
    (net (code "48") (name "Net-(U1-RT_CLK)") (class "Default")
      (node (ref "R19") (pin "2") (pinfunction "2_2") (pintype "passive"))
      (node (ref "U1") (pin "1") (pinfunction "RT_CLK_1") (pintype "input"))
    )
    (net (code "49") (name "Net-(U1-SO2)") (class "Default")
      (node (ref "R42") (pin "2") (pinfunction "2_2") (pintype "passive"))
      (node (ref "U1") (pin "26") (pinfunction "SO2_26") (pintype "output"))
    )
    (net (code "50") (name "Net-(U1-VSENSE)") (class "Default")
      (node (ref "R21") (pin "1") (pinfunction "1_1") (pintype "passive"))
      (node (ref "R22") (pin "1") (pinfunction "1_1") (pintype "passive"))
      (node (ref "U1") (pin "3") (pinfunction "VSENSE_3") (pintype "input"))
    )
    (net (code "51") (name "Net-(U2-FILT)") (class "Default")
      (node (ref "C22") (pin "1") (pinfunction "1_1") (pintype "passive"))
      (node (ref "U2") (pin "6") (pinfunction "FILT_6") (pintype "bidirectional"))
    )
    (net (code "52") (name "Net-(U3-FILT)") (class "Default")
      (node (ref "C23") (pin "1") (pinfunction "1_1") (pintype "passive"))
      (node (ref "U3") (pin "6") (pinfunction "FILT_6") (pintype "bidirectional"))
    )
    (net (code "53") (name "PWM_A") (class "Default")
      (node (ref "JP1") (pin "3") (pinfunction "3_3") (pintype "passive"))
      (node (ref "U1") (pin "17") (pinfunction "INH_A_17") (pintype "input"))
    )
    (net (code "54") (name "PWM_B") (class "Default")
      (node (ref "JP1") (pin "5") (pinfunction "5_5") (pintype "passive"))
      (node (ref "U1") (pin "19") (pinfunction "INH_B_19") (pintype "input"))
    )
    (net (code "55") (name "PWM_C") (class "Default")
      (node (ref "JP1") (pin "7") (pinfunction "7_7") (pintype "passive"))
      (node (ref "U1") (pin "21") (pinfunction "INH_C_21") (pintype "input"))
    )
    (net (code "56") (name "R_B") (class "Default")
      (node (ref "C2") (pin "2") (pinfunction "2_2") (pintype "passive"))
      (node (ref "D3") (pin "2") (pinfunction "A_2") (pintype "passive"))
      (node (ref "R17") (pin "2") (pinfunction "2_2") (pintype "passive"))
      (node (ref "R3") (pin "1") (pinfunction "1_1") (pintype "passive"))
      (node (ref "R33") (pin "2") (pinfunction "2_2") (pintype "passive"))
      (node (ref "S_BH") (pin "2") (pinfunction "S_2") (pintype "passive"))
      (node (ref "S_BH") (pin "3") (pinfunction "S_3") (pintype "passive"))
      (node (ref "S_BH") (pin "5") (pinfunction "S_5") (pintype "passive"))
      (node (ref "S_BH") (pin "6") (pinfunction "S_6") (pintype "passive"))
      (node (ref "S_BH") (pin "7") (pinfunction "S_7") (pintype "passive"))
      (node (ref "S_BL") (pin "4") (pinfunction "D_4") (pintype "passive"))
      (node (ref "U1") (pin "41") (pinfunction "SH_B_41") (pintype "input"))
      (node (ref "U2") (pin "1") (pinfunction "IP+_1") (pintype "bidirectional"))
      (node (ref "U2") (pin "2") (pinfunction "IP+_2") (pintype "bidirectional"))
    )
    (net (code "57") (name "R_C") (class "Default")
      (node (ref "C3") (pin "2") (pinfunction "2_2") (pintype "passive"))
      (node (ref "D5") (pin "2") (pinfunction "A_2") (pintype "passive"))
      (node (ref "R18") (pin "2") (pinfunction "2_2") (pintype "passive"))
      (node (ref "R36") (pin "2") (pinfunction "2_2") (pintype "passive"))
      (node (ref "R5") (pin "1") (pinfunction "1_1") (pintype "passive"))
      (node (ref "S_CH") (pin "2") (pinfunction "S_2") (pintype "passive"))
      (node (ref "S_CH") (pin "3") (pinfunction "S_3") (pintype "passive"))
      (node (ref "S_CH") (pin "5") (pinfunction "S_5") (pintype "passive"))
      (node (ref "S_CH") (pin "6") (pinfunction "S_6") (pintype "passive"))
      (node (ref "S_CH") (pin "7") (pinfunction "S_7") (pintype "passive"))
      (node (ref "S_CL") (pin "4") (pinfunction "D_4") (pintype "passive"))
      (node (ref "U1") (pin "36") (pinfunction "SH_C_36") (pintype "input"))
      (node (ref "U3") (pin "1") (pinfunction "IP+_1") (pintype "bidirectional"))
      (node (ref "U3") (pin "2") (pinfunction "IP+_2") (pintype "bidirectional"))
    )
    (net (code "58") (name "V+") (class "Default")
      (node (ref "C24") (pin "1") (pinfunction "1_1") (pintype "passive"))
      (node (ref "C25") (pin "1") (pinfunction "1_1") (pintype "passive"))
      (node (ref "C26") (pin "1") (pinfunction "1_1") (pintype "passive"))
      (node (ref "C27") (pin "1") (pinfunction "1_1") (pintype "passive"))
      (node (ref "C28") (pin "1") (pinfunction "1_1") (pintype "passive"))
      (node (ref "C29") (pin "1") (pinfunction "1_1") (pintype "passive"))
      (node (ref "C30") (pin "1") (pinfunction "1_1") (pintype "passive"))
      (node (ref "C31") (pin "1") (pinfunction "1_1") (pintype "passive"))
      (node (ref "C32") (pin "1") (pinfunction "1_1") (pintype "passive"))
      (node (ref "C33") (pin "1") (pinfunction "1_1") (pintype "passive"))
      (node (ref "C34") (pin "1") (pinfunction "1_1") (pintype "passive"))
      (node (ref "C35") (pin "1") (pinfunction "1_1") (pintype "passive"))
      (node (ref "C36") (pin "1") (pinfunction "1_1") (pintype "passive"))
      (node (ref "C37") (pin "1") (pinfunction "1_1") (pintype "passive"))
      (node (ref "C38") (pin "1") (pinfunction "1_1") (pintype "passive"))
      (node (ref "C39") (pin "1") (pinfunction "1_1") (pintype "passive"))
      (node (ref "R30") (pin "2") (pinfunction "2_2") (pintype "passive"))
      (node (ref "S_AH") (pin "4") (pinfunction "D_4") (pintype "passive"))
      (node (ref "S_BH") (pin "4") (pinfunction "D_4") (pintype "passive"))
      (node (ref "S_CH") (pin "4") (pinfunction "D_4") (pintype "passive"))
      (node (ref "U1") (pin "29") (pinfunction "PVDD1_29") (pintype "power_in"))
      (node (ref "U1") (pin "53") (pinfunction "PVDD2_1_53") (pintype "power_in"))
      (node (ref "U1") (pin "54") (pinfunction "PVDD2_2_54") (pintype "power_in"))
    )
    (net (code "59") (name "V-") (class "Default")
      (node (ref "FB1") (pin "2") (pinfunction "2_2") (pintype "passive"))
      (node (ref "R13") (pin "1") (pinfunction "1_1") (pintype "passive"))
      (node (ref "R14") (pin "1") (pinfunction "1_1") (pintype "passive"))
      (node (ref "R31") (pin "1") (pinfunction "1_1") (pintype "passive"))
      (node (ref "R34") (pin "1") (pinfunction "1_1") (pintype "passive"))
      (node (ref "R37") (pin "1") (pinfunction "1_1") (pintype "passive"))
      (node (ref "R40") (pin "1") (pinfunction "1_1") (pintype "passive"))
      (node (ref "R43") (pin "2") (pinfunction "2_2") (pintype "passive"))
      (node (ref "U1") (pin "31") (pinfunction "SN2_31") (pintype "input"))
    )
    (net (code "60") (name "VCC") (class "Default")
      (node (ref "C12") (pin "1") (pinfunction "1_1") (pintype "passive"))
      (node (ref "C9") (pin "1") (pinfunction "1_1") (pintype "passive"))
      (node (ref "L1") (pin "P$1") (pinfunction "1_P$1") (pintype "passive"))
      (node (ref "R21") (pin "2") (pinfunction "2_2") (pintype "passive"))
      (node (ref "U4") (pin "1") (pinfunction "IN_1") (pintype "input"))
      (node (ref "U4") (pin "3") (pinfunction "EN_3") (pintype "input"))
    )
    (net (code "61") (name "V_A") (class "Default")
      (node (ref "C18") (pin "2") (pinfunction "2_2") (pintype "passive"))
      (node (ref "JP1") (pin "11") (pinfunction "11_11") (pintype "passive"))
      (node (ref "R32") (pin "2") (pinfunction "2_2") (pintype "passive"))
    )
    (net (code "62") (name "V_B") (class "Default")
      (node (ref "C21") (pin "2") (pinfunction "2_2") (pintype "passive"))
      (node (ref "JP1") (pin "12") (pinfunction "12_12") (pintype "passive"))
      (node (ref "R41") (pin "2") (pinfunction "2_2") (pintype "passive"))
    )
    (net (code "63") (name "V_C") (class "Default")
      (node (ref "C20") (pin "2") (pinfunction "2_2") (pintype "passive"))
      (node (ref "JP1") (pin "13") (pinfunction "13_13") (pintype "passive"))
      (node (ref "R38") (pin "2") (pinfunction "2_2") (pintype "passive"))
    )
    (net (code "64") (name "V_LOW") (class "Default")
      (node (ref "C24") (pin "2") (pinfunction "2_2") (pintype "passive"))
      (node (ref "C25") (pin "2") (pinfunction "2_2") (pintype "passive"))
      (node (ref "C26") (pin "2") (pinfunction "2_2") (pintype "passive"))
      (node (ref "C27") (pin "2") (pinfunction "2_2") (pintype "passive"))
      (node (ref "C28") (pin "2") (pinfunction "2_2") (pintype "passive"))
      (node (ref "C29") (pin "2") (pinfunction "2_2") (pintype "passive"))
      (node (ref "C30") (pin "2") (pinfunction "2_2") (pintype "passive"))
      (node (ref "C31") (pin "2") (pinfunction "2_2") (pintype "passive"))
      (node (ref "C32") (pin "2") (pinfunction "2_2") (pintype "passive"))
      (node (ref "C33") (pin "2") (pinfunction "2_2") (pintype "passive"))
      (node (ref "C34") (pin "2") (pinfunction "2_2") (pintype "passive"))
      (node (ref "C35") (pin "2") (pinfunction "2_2") (pintype "passive"))
      (node (ref "C36") (pin "2") (pinfunction "2_2") (pintype "passive"))
      (node (ref "C37") (pin "2") (pinfunction "2_2") (pintype "passive"))
      (node (ref "C38") (pin "2") (pinfunction "2_2") (pintype "passive"))
      (node (ref "C39") (pin "2") (pinfunction "2_2") (pintype "passive"))
      (node (ref "D2") (pin "2") (pinfunction "A_2") (pintype "passive"))
      (node (ref "D4") (pin "2") (pinfunction "A_2") (pintype "passive"))
      (node (ref "D6") (pin "2") (pinfunction "A_2") (pintype "passive"))
      (node (ref "R13") (pin "2") (pinfunction "2_2") (pintype "passive"))
      (node (ref "R14") (pin "2") (pinfunction "2_2") (pintype "passive"))
      (node (ref "R2") (pin "1") (pinfunction "1_1") (pintype "passive"))
      (node (ref "R4") (pin "1") (pinfunction "1_1") (pintype "passive"))
      (node (ref "R6") (pin "1") (pinfunction "1_1") (pintype "passive"))
      (node (ref "S_AL") (pin "2") (pinfunction "S_2") (pintype "passive"))
      (node (ref "S_AL") (pin "3") (pinfunction "S_3") (pintype "passive"))
      (node (ref "S_AL") (pin "5") (pinfunction "S_5") (pintype "passive"))
      (node (ref "S_AL") (pin "6") (pinfunction "S_6") (pintype "passive"))
      (node (ref "S_AL") (pin "7") (pinfunction "S_7") (pintype "passive"))
      (node (ref "S_BL") (pin "2") (pinfunction "S_2") (pintype "passive"))
      (node (ref "S_BL") (pin "3") (pinfunction "S_3") (pintype "passive"))
      (node (ref "S_BL") (pin "5") (pinfunction "S_5") (pintype "passive"))
      (node (ref "S_BL") (pin "6") (pinfunction "S_6") (pintype "passive"))
      (node (ref "S_BL") (pin "7") (pinfunction "S_7") (pintype "passive"))
      (node (ref "S_CL") (pin "2") (pinfunction "S_2") (pintype "passive"))
      (node (ref "S_CL") (pin "3") (pinfunction "S_3") (pintype "passive"))
      (node (ref "S_CL") (pin "5") (pinfunction "S_5") (pintype "passive"))
      (node (ref "S_CL") (pin "6") (pinfunction "S_6") (pintype "passive"))
      (node (ref "S_CL") (pin "7") (pinfunction "S_7") (pintype "passive"))
      (node (ref "U1") (pin "30") (pinfunction "SP2_30") (pintype "input"))
      (node (ref "U1") (pin "34") (pinfunction "SL_C_34") (pintype "input"))
      (node (ref "U1") (pin "39") (pinfunction "SL_B_39") (pintype "input"))
      (node (ref "U1") (pin "44") (pinfunction "SL_A_44") (pintype "input"))
    )
    (net (code "65") (name "V_P") (class "Default")
      (node (ref "C19") (pin "2") (pinfunction "2_2") (pintype "passive"))
      (node (ref "JP1") (pin "15") (pinfunction "15_15") (pintype "passive"))
      (node (ref "R35") (pin "2") (pinfunction "2_2") (pintype "passive"))
    )
    (net (code "66") (name "unconnected-(JP2-Pad2)") (class "Default")
      (node (ref "JP2") (pin "2") (pinfunction "2_2") (pintype "passive"))
    )
    (net (code "67") (name "unconnected-(JP2-Pad3)") (class "Default")
      (node (ref "JP2") (pin "3") (pinfunction "3_3") (pintype "passive"))
    )
    (net (code "68") (name "unconnected-(JP2-Pad4)") (class "Default")
      (node (ref "JP2") (pin "4") (pinfunction "4_4") (pintype "passive"))
    )
    (net (code "69") (name "unconnected-(JP2-Pad5)") (class "Default")
      (node (ref "JP2") (pin "5") (pinfunction "5_5") (pintype "passive"))
    )
    (net (code "70") (name "unconnected-(JP2-Pad6)") (class "Default")
      (node (ref "JP2") (pin "6") (pinfunction "6_6") (pintype "passive"))
    )
    (net (code "71") (name "unconnected-(JP2-Pad7)") (class "Default")
      (node (ref "JP2") (pin "7") (pinfunction "7_7") (pintype "passive"))
    )
    (net (code "72") (name "unconnected-(JP2-Pad8)") (class "Default")
      (node (ref "JP2") (pin "8") (pinfunction "8_8") (pintype "passive"))
    )
    (net (code "73") (name "unconnected-(JP2-Pad9)") (class "Default")
      (node (ref "JP2") (pin "9") (pinfunction "9_9") (pintype "passive"))
    )
    (net (code "74") (name "unconnected-(JP2-Pad10)") (class "Default")
      (node (ref "JP2") (pin "10") (pinfunction "10_10") (pintype "passive"))
    )
    (net (code "75") (name "unconnected-(JP2-Pad11)") (class "Default")
      (node (ref "JP2") (pin "11") (pinfunction "11_11") (pintype "passive"))
    )
    (net (code "76") (name "unconnected-(JP2-Pad12)") (class "Default")
      (node (ref "JP2") (pin "12") (pinfunction "12_12") (pintype "passive"))
    )
    (net (code "77") (name "unconnected-(JP2-Pad13)") (class "Default")
      (node (ref "JP2") (pin "13") (pinfunction "13_13") (pintype "passive"))
    )
    (net (code "78") (name "unconnected-(JP2-Pad14)") (class "Default")
      (node (ref "JP2") (pin "14") (pinfunction "14_14") (pintype "passive"))
    )
    (net (code "79") (name "unconnected-(JP2-Pad15)") (class "Default")
      (node (ref "JP2") (pin "15") (pinfunction "15_15") (pintype "passive"))
    )
    (net (code "80") (name "unconnected-(U1-BIAS-Pad49)") (class "Default")
      (node (ref "U1") (pin "49") (pinfunction "BIAS_49") (pintype "input"))
    )
    (net (code "81") (name "unconnected-(U1-EN_BUCK-Pad55)") (class "Default")
      (node (ref "U1") (pin "55") (pinfunction "EN_BUCK_55") (pintype "bidirectional"))
    )
    (net (code "82") (name "unconnected-(U1-PWRGD-Pad4)") (class "Default")
      (node (ref "U1") (pin "4") (pinfunction "PWRGD_4") (pintype "output"))
    )
    (net (code "83") (name "unconnected-(U1-SN1-Pad33)") (class "Default")
      (node (ref "U1") (pin "33") (pinfunction "SN1_33") (pintype "input"))
    )
    (net (code "84") (name "unconnected-(U1-SO1-Pad25)") (class "Default")
      (node (ref "U1") (pin "25") (pinfunction "SO1_25") (pintype "output"))
    )
    (net (code "85") (name "unconnected-(U1-SP1-Pad32)") (class "Default")
      (node (ref "U1") (pin "32") (pinfunction "SP1_32") (pintype "input"))
    )
    (net (code "86") (name "unconnected-(U1-SS_TR-Pad56)") (class "Default")
      (node (ref "U1") (pin "56") (pinfunction "SS_TR_56") (pintype "bidirectional"))
    )
    (net (code "87") (name "unconnected-(U1-~{FAULT}-Pad6)") (class "Default")
      (node (ref "U1") (pin "6") (pinfunction "~{FAULT}_6") (pintype "output"))
    )
    (net (code "88") (name "unconnected-(U1-~{OCTW}-Pad5)") (class "Default")
      (node (ref "U1") (pin "5") (pinfunction "~{OCTW}_5") (pintype "output"))
    )
    (net (code "89") (name "unconnected-(U4-BP-Pad4)") (class "Default")
      (node (ref "U4") (pin "4") (pinfunction "BP_4") (pintype "input"))
    )
    (net (code "90") (name "unconnected-(U5-BP-Pad4)") (class "Default")
      (node (ref "U5") (pin "4") (pinfunction "BP_4") (pintype "input"))
    )
    (net (code "91") (name "~{PWM_A}") (class "Default")
      (node (ref "JP1") (pin "4") (pinfunction "4_4") (pintype "passive"))
      (node (ref "U1") (pin "18") (pinfunction "INL_A_18") (pintype "input"))
    )
    (net (code "92") (name "~{PWM_B}") (class "Default")
      (node (ref "JP1") (pin "6") (pinfunction "6_6") (pintype "passive"))
      (node (ref "U1") (pin "20") (pinfunction "INL_B_20") (pintype "input"))
    )
    (net (code "93") (name "~{PWM_C}") (class "Default")
      (node (ref "JP1") (pin "8") (pinfunction "8_8") (pintype "passive"))
      (node (ref "U1") (pin "22") (pinfunction "INL_C_22") (pintype "input"))
    )
  )
)
